# Main_Board_2X-SOLAR_5V-DCDC.net
KiCad netlist of a schematic drawn in EAGLE
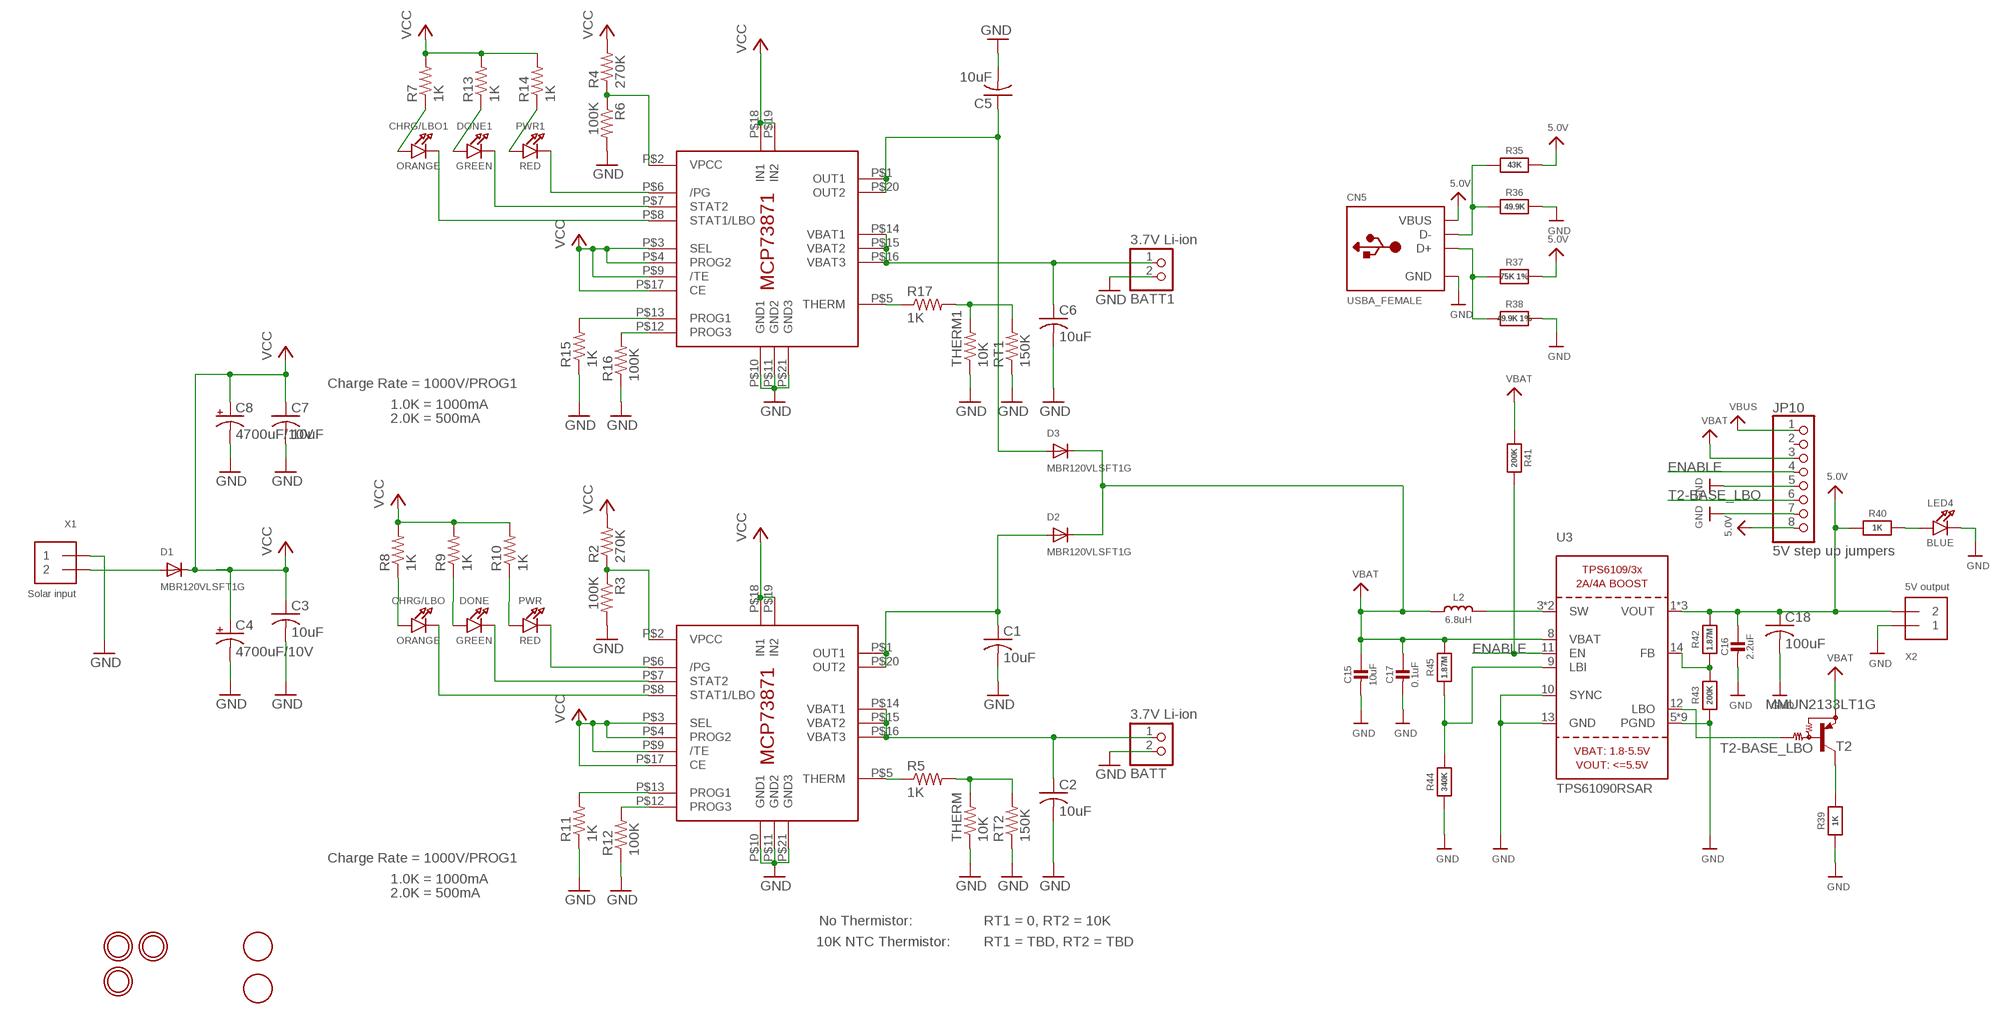
[diagram p0: schematic, sheet 1]

(export (version "E")
  (design (tool "Eeschema 10.0.6"))
  (components
    (comp (ref "BATT")
      (value "3.7V Li-ion")
      (footprint "eagle-import:JST-PH-2-SMT-RA")
      (libsource (lib "eagle-import") (part "JST_2PIN-SMT-RA"))
    )
    (comp (ref "BATT1")
      (value "3.7V Li-ion")
      (footprint "eagle-import:JST-PH-2-SMT-RA")
      (libsource (lib "eagle-import") (part "JST_2PIN-SMT-RA"))
    )
    (comp (ref "C1")
      (value "10uF")
      (footprint "eagle-import:C0805K")
      (libsource (lib "eagle-import") (part "C-USC0805K"))
    )
    (comp (ref "C2")
      (value "10uF")
      (footprint "eagle-import:C0805K")
      (libsource (lib "eagle-import") (part "C-USC0805K"))
    )
    (comp (ref "C3")
      (value "10uF")
      (footprint "eagle-import:C0805K")
      (libsource (lib "eagle-import") (part "C-USC0805K"))
    )
    (comp (ref "C4")
      (value "4700uF/10V")
      (footprint "eagle-import:E5-13")
      (libsource (lib "eagle-import") (part "CPOL-USE5-13"))
    )
    (comp (ref "C5")
      (value "10uF")
      (footprint "eagle-import:C0805K")
      (libsource (lib "eagle-import") (part "C-USC0805K"))
    )
    (comp (ref "C6")
      (value "10uF")
      (footprint "eagle-import:C0805K")
      (libsource (lib "eagle-import") (part "C-USC0805K"))
    )
    (comp (ref "C7")
      (value "10uF")
      (footprint "eagle-import:C0805K")
      (libsource (lib "eagle-import") (part "C-USC0805K"))
    )
    (comp (ref "C8")
      (value "4700uF/10V")
      (footprint "eagle-import:E5-13")
      (libsource (lib "eagle-import") (part "CPOL-USE5-13"))
    )
    (comp (ref "C15")
      (value "10uF")
      (footprint "eagle-import:0805-NO")
      (libsource (lib "eagle-import") (part "CAP_CERAMIC0805-NOOUTLINE"))
    )
    (comp (ref "C16")
      (value "2.2uF")
      (footprint "eagle-import:0805-NO")
      (libsource (lib "eagle-import") (part "CAP_CERAMIC0805-NOOUTLINE"))
    )
    (comp (ref "C17")
      (value "0.1uF")
      (footprint "eagle-import:0805_10MGAP")
      (libsource (lib "eagle-import") (part "CAP_CERAMIC0805_10MGAP"))
    )
    (comp (ref "C18")
      (value "100uF")
      (footprint "eagle-import:C1210")
      (libsource (lib "eagle-import") (part "rcl_C-USC1210"))
    )
    (comp (ref "CHRG/LBO")
      (value "ORANGE")
      (footprint "eagle-import:CHIPLED_0805_NOOUTLINE")
      (libsource (lib "eagle-import") (part "LED0805_NOOUTLINE"))
    )
    (comp (ref "CHRG/LBO1")
      (value "ORANGE")
      (footprint "eagle-import:CHIPLED_0805_NOOUTLINE")
      (libsource (lib "eagle-import") (part "LED0805_NOOUTLINE"))
    )
    (comp (ref "CN5")
      (value "USBA_FEMALE")
      (footprint "eagle-import:USB_HOST-PTH")
      (libsource (lib "eagle-import") (part "USB_TYPEAPTHFML"))
    )
    (comp (ref "D1")
      (value "MBR120VLSFT1G")
      (footprint "eagle-import:SOD-123")
      (libsource (lib "eagle-import") (part "DIODESOD-123"))
    )
    (comp (ref "D2")
      (value "MBR120VLSFT1G")
      (footprint "eagle-import:SOD-123")
      (libsource (lib "eagle-import") (part "DIODESOD-123"))
    )
    (comp (ref "D3")
      (value "MBR120VLSFT1G")
      (footprint "eagle-import:SOD-123")
      (libsource (lib "eagle-import") (part "DIODESOD-123"))
    )
    (comp (ref "DONE")
      (value "GREEN")
      (footprint "eagle-import:CHIPLED_0805_NOOUTLINE")
      (libsource (lib "eagle-import") (part "LED0805_NOOUTLINE"))
    )
    (comp (ref "DONE1")
      (value "GREEN")
      (footprint "eagle-import:CHIPLED_0805_NOOUTLINE")
      (libsource (lib "eagle-import") (part "LED0805_NOOUTLINE"))
    )
    (comp (ref "IC1")
      (value "MCP73871")
      (footprint "eagle-import:QFN20_4MM")
      (libsource (lib "eagle-import") (part "MCP73871"))
    )
    (comp (ref "IC2")
      (value "MCP73871")
      (footprint "eagle-import:QFN20_4MM")
      (libsource (lib "eagle-import") (part "MCP73871"))
    )
    (comp (ref "JP10")
      (value "5V step up jumpers")
      (footprint "eagle-import:1X08_ROUND")
      (libsource (lib "eagle-import") (part "HEADER-1X8ROUND"))
    )
    (comp (ref "L2")
      (value "6.8uH")
      (footprint "eagle-import:INDUCTOR_5X5MM_TDK_VLC5045")
      (libsource (lib "eagle-import") (part "INDUCTORTDK_VLC5045"))
    )
    (comp (ref "LED4")
      (value "BLUE")
      (footprint "eagle-import:CHIPLED_0805_NOOUTLINE")
      (libsource (lib "eagle-import") (part "LED0805_NOOUTLINE"))
    )
    (comp (ref "PWR")
      (value "RED")
      (footprint "eagle-import:CHIPLED_0805_NOOUTLINE")
      (libsource (lib "eagle-import") (part "LED0805_NOOUTLINE"))
    )
    (comp (ref "PWR1")
      (value "RED")
      (footprint "eagle-import:CHIPLED_0805_NOOUTLINE")
      (libsource (lib "eagle-import") (part "LED0805_NOOUTLINE"))
    )
    (comp (ref "R2")
      (value "270K")
      (footprint "eagle-import:R0805")
      (libsource (lib "eagle-import") (part "R-US_R0805"))
    )
    (comp (ref "R3")
      (value "100K")
      (footprint "eagle-import:R0805")
      (libsource (lib "eagle-import") (part "R-US_R0805"))
    )
    (comp (ref "R4")
      (value "270K")
      (footprint "eagle-import:R0805")
      (libsource (lib "eagle-import") (part "R-US_R0805"))
    )
    (comp (ref "R5")
      (value "1K")
      (footprint "eagle-import:M0805")
      (libsource (lib "eagle-import") (part "R-US_M0805"))
    )
    (comp (ref "R6")
      (value "100K")
      (footprint "eagle-import:R0805")
      (libsource (lib "eagle-import") (part "R-US_R0805"))
    )
    (comp (ref "R7")
      (value "1K")
      (footprint "eagle-import:R0805")
      (libsource (lib "eagle-import") (part "R-US_R0805"))
    )
    (comp (ref "R8")
      (value "1K")
      (footprint "eagle-import:R0805")
      (libsource (lib "eagle-import") (part "R-US_R0805"))
    )
    (comp (ref "R9")
      (value "1K")
      (footprint "eagle-import:R0805")
      (libsource (lib "eagle-import") (part "R-US_R0805"))
    )
    (comp (ref "R10")
      (value "1K")
      (footprint "eagle-import:R0805")
      (libsource (lib "eagle-import") (part "R-US_R0805"))
    )
    (comp (ref "R11")
      (value "1K")
      (footprint "eagle-import:0805-THM")
      (libsource (lib "eagle-import") (part "R-US_FLIPFLOP"))
    )
    (comp (ref "R12")
      (value "100K")
      (footprint "eagle-import:R0805")
      (libsource (lib "eagle-import") (part "R-US_R0805"))
    )
    (comp (ref "R13")
      (value "1K")
      (footprint "eagle-import:R0805")
      (libsource (lib "eagle-import") (part "R-US_R0805"))
    )
    (comp (ref "R14")
      (value "1K")
      (footprint "eagle-import:R0805")
      (libsource (lib "eagle-import") (part "R-US_R0805"))
    )
    (comp (ref "R15")
      (value "1K")
      (footprint "eagle-import:0805-THM")
      (libsource (lib "eagle-import") (part "R-US_FLIPFLOP"))
    )
    (comp (ref "R16")
      (value "100K")
      (footprint "eagle-import:R0805")
      (libsource (lib "eagle-import") (part "R-US_R0805"))
    )
    (comp (ref "R17")
      (value "1K")
      (footprint "eagle-import:M0805")
      (libsource (lib "eagle-import") (part "R-US_M0805"))
    )
    (comp (ref "R35")
      (value "43K")
      (footprint "eagle-import:0805-NO")
      (libsource (lib "eagle-import") (part "RESISTOR0805_NOOUTLINE"))
    )
    (comp (ref "R36")
      (value "49.9K")
      (footprint "eagle-import:0805-NO")
      (libsource (lib "eagle-import") (part "RESISTOR0805_NOOUTLINE"))
    )
    (comp (ref "R37")
      (value "75K 1%")
      (footprint "eagle-import:0805-NO")
      (libsource (lib "eagle-import") (part "RESISTOR0805_NOOUTLINE"))
    )
    (comp (ref "R38")
      (value "49.9K 1%")
      (footprint "eagle-import:0805-NO")
      (libsource (lib "eagle-import") (part "RESISTOR0805_NOOUTLINE"))
    )
    (comp (ref "R39")
      (value "1K")
      (footprint "eagle-import:0805-NO")
      (libsource (lib "eagle-import") (part "RESISTOR0805_NOOUTLINE"))
    )
    (comp (ref "R40")
      (value "1K")
      (footprint "eagle-import:0805-NO")
      (libsource (lib "eagle-import") (part "RESISTOR0805_NOOUTLINE"))
    )
    (comp (ref "R41")
      (value "200K")
      (footprint "eagle-import:0805-NO")
      (libsource (lib "eagle-import") (part "RESISTOR0805_NOOUTLINE"))
    )
    (comp (ref "R42")
      (value "1.87M")
      (footprint "eagle-import:0805-NO")
      (libsource (lib "eagle-import") (part "RESISTOR0805_NOOUTLINE"))
    )
    (comp (ref "R43")
      (value "200K")
      (footprint "eagle-import:0805-NO")
      (libsource (lib "eagle-import") (part "RESISTOR0805_NOOUTLINE"))
    )
    (comp (ref "R44")
      (value "340K")
      (footprint "eagle-import:_0805MP")
      (libsource (lib "eagle-import") (part "RESISTOR_0805MP"))
    )
    (comp (ref "R45")
      (value "1.87M")
      (footprint "eagle-import:_0805MP")
      (libsource (lib "eagle-import") (part "RESISTOR_0805MP"))
    )
    (comp (ref "RT1")
      (value "150K")
      (footprint "eagle-import:M0805")
      (libsource (lib "eagle-import") (part "R-US_M0805"))
    )
    (comp (ref "RT2")
      (value "150K")
      (footprint "eagle-import:M0805")
      (libsource (lib "eagle-import") (part "R-US_M0805"))
    )
    (comp (ref "T2")
      (value "MMUN2133LT1G")
      (footprint "eagle-import:SC59-BEC")
      (libsource (lib "eagle-import") (part "-PNP_DRIVER-SC59-BECMUN2114T1"))
    )
    (comp (ref "THERM")
      (value "10K")
      (footprint "eagle-import:0805-THM")
      (libsource (lib "eagle-import") (part "R-US_FLIPFLOP"))
    )
    (comp (ref "THERM1")
      (value "10K")
      (footprint "eagle-import:0805-THM")
      (libsource (lib "eagle-import") (part "R-US_FLIPFLOP"))
    )
    (comp (ref "U$1")
      (value "MOUNTINGHOLE2.5")
      (footprint "eagle-import:MOUNTINGHOLE_2.5_PLATED")
      (libsource (lib "eagle-import") (part "MOUNTINGHOLE2.5"))
    )
    (comp (ref "U$3")
      (value "FIDUCIAL")
      (footprint "eagle-import:FIDUCIAL_1MM")
      (libsource (lib "eagle-import") (part "FIDUCIAL"))
    )
    (comp (ref "U$4")
      (value "MOUNTINGHOLE2.5")
      (footprint "eagle-import:MOUNTINGHOLE_2.5_PLATED")
      (libsource (lib "eagle-import") (part "MOUNTINGHOLE2.5"))
    )
    (comp (ref "U$6")
      (value "MOUNTINGHOLE2.5")
      (footprint "eagle-import:MOUNTINGHOLE_2.5_PLATED")
      (libsource (lib "eagle-import") (part "MOUNTINGHOLE2.5"))
    )
    (comp (ref "U$8")
      (value "FIDUCIAL")
      (footprint "eagle-import:FIDUCIAL_1MM")
      (libsource (lib "eagle-import") (part "FIDUCIAL"))
    )
    (comp (ref "U3")
      (value "TPS61090RSAR")
      (footprint "eagle-import:PVQFN-16")
      (libsource (lib "eagle-import") (part "VREG_TPS6103X"))
    )
    (comp (ref "X1")
      (value "Solar input")
      (footprint "eagle-import:TERMBLOCK_1X2-3.5MM")
      (libsource (lib "eagle-import") (part "TERMBLOCK_1X2"))
    )
    (comp (ref "X2")
      (value "5V output")
      (footprint "eagle-import:TERMBLOCK_1X2-3.5MM")
      (libsource (lib "eagle-import") (part "TERMBLOCK_1X2"))
    )
  )
  (nets
    (net (code "1") (name "/ENABLE") (class "Default")
      (node (ref "JP10") (pin "4") (pinfunction "4_4") (pintype "passive"))
      (node (ref "R41") (pin "2") (pinfunction "2_2") (pintype "passive"))
      (node (ref "U3") (pin "11") (pinfunction "EN_11") (pintype "input"))
    )
    (net (code "2") (name "/T2-BASE_LBO") (class "Default")
      (node (ref "JP10") (pin "6") (pinfunction "6_6") (pintype "passive"))
      (node (ref "T2") (pin "B") (pinfunction "B_B") (pintype "passive"))
      (node (ref "U3") (pin "12") (pinfunction "LBO_12") (pintype "output"))
    )
    (net (code "3") (name "5.0V") (class "Default")
      (node (ref "C16") (pin "1") (pinfunction "1_1") (pintype "passive"))
      (node (ref "C18") (pin "1") (pinfunction "1_1") (pintype "passive"))
      (node (ref "CN5") (pin "VBUS") (pinfunction "VBUS_VBUS") (pintype "power_in"))
      (node (ref "JP10") (pin "8") (pinfunction "8_8") (pintype "passive"))
      (node (ref "R35") (pin "2") (pinfunction "2_2") (pintype "passive"))
      (node (ref "R37") (pin "2") (pinfunction "2_2") (pintype "passive"))
      (node (ref "R40") (pin "1") (pinfunction "1_1") (pintype "passive"))
      (node (ref "R42") (pin "2") (pinfunction "2_2") (pintype "passive"))
      (node (ref "U3") (pin "1") (pinfunction "VOUT_1") (pintype "power_in"))
      (node (ref "U3") (pin "15") (pinfunction "VOUT_15") (pintype "power_in"))
      (node (ref "U3") (pin "16") (pinfunction "VOUT_16") (pintype "power_in"))
      (node (ref "X2") (pin "2") (pinfunction "2_2") (pintype "passive"))
    )
    (net (code "4") (name "GND") (class "Default")
      (node (ref "BATT") (pin "2") (pinfunction "1_2") (pintype "passive"))
      (node (ref "BATT1") (pin "2") (pinfunction "1_2") (pintype "passive"))
      (node (ref "C1") (pin "2") (pinfunction "2_2") (pintype "passive"))
      (node (ref "C15") (pin "2") (pinfunction "2_2") (pintype "passive"))
      (node (ref "C16") (pin "2") (pinfunction "2_2") (pintype "passive"))
      (node (ref "C17") (pin "2") (pinfunction "2_2") (pintype "passive"))
      (node (ref "C18") (pin "2") (pinfunction "2_2") (pintype "passive"))
      (node (ref "C2") (pin "2") (pinfunction "2_2") (pintype "passive"))
      (node (ref "C3") (pin "2") (pinfunction "2_2") (pintype "passive"))
      (node (ref "C4") (pin "-") (pinfunction "-_-") (pintype "passive"))
      (node (ref "C5") (pin "2") (pinfunction "2_2") (pintype "passive"))
      (node (ref "C6") (pin "2") (pinfunction "2_2") (pintype "passive"))
      (node (ref "C7") (pin "2") (pinfunction "2_2") (pintype "passive"))
      (node (ref "C8") (pin "-") (pinfunction "-_-") (pintype "passive"))
      (node (ref "CN5") (pin "GND") (pinfunction "GND_GND") (pintype "power_in"))
      (node (ref "IC1") (pin "P$10") (pinfunction "GND1_P$10") (pintype "power_in"))
      (node (ref "IC1") (pin "P$11") (pinfunction "GND2_P$11") (pintype "power_in"))
      (node (ref "IC1") (pin "P$21") (pinfunction "GND3_P$21") (pintype "power_in"))
      (node (ref "IC2") (pin "P$10") (pinfunction "GND1_P$10") (pintype "power_in"))
      (node (ref "IC2") (pin "P$11") (pinfunction "GND2_P$11") (pintype "power_in"))
      (node (ref "IC2") (pin "P$21") (pinfunction "GND3_P$21") (pintype "power_in"))
      (node (ref "JP10") (pin "5") (pinfunction "5_5") (pintype "passive"))
      (node (ref "JP10") (pin "7") (pinfunction "7_7") (pintype "passive"))
      (node (ref "LED4") (pin "C") (pinfunction "C_C") (pintype "passive"))
      (node (ref "R11") (pin "1") (pinfunction "1_1") (pintype "passive"))
      (node (ref "R12") (pin "1") (pinfunction "1_1") (pintype "passive"))
      (node (ref "R15") (pin "1") (pinfunction "1_1") (pintype "passive"))
      (node (ref "R16") (pin "1") (pinfunction "1_1") (pintype "passive"))
      (node (ref "R3") (pin "2") (pinfunction "2_2") (pintype "passive"))
      (node (ref "R36") (pin "2") (pinfunction "2_2") (pintype "passive"))
      (node (ref "R38") (pin "2") (pinfunction "2_2") (pintype "passive"))
      (node (ref "R39") (pin "1") (pinfunction "1_1") (pintype "passive"))
      (node (ref "R43") (pin "1") (pinfunction "1_1") (pintype "passive"))
      (node (ref "R44") (pin "1") (pinfunction "1_1") (pintype "passive"))
      (node (ref "R6") (pin "2") (pinfunction "2_2") (pintype "passive"))
      (node (ref "RT1") (pin "1") (pinfunction "1_1") (pintype "passive"))
      (node (ref "RT2") (pin "1") (pinfunction "1_1") (pintype "passive"))
      (node (ref "THERM") (pin "1") (pinfunction "1_1") (pintype "passive"))
      (node (ref "THERM1") (pin "1") (pinfunction "1_1") (pintype "passive"))
      (node (ref "U3") (pin "10") (pinfunction "SYNC_10") (pintype "input"))
      (node (ref "U3") (pin "13") (pinfunction "GND_13") (pintype "power_in"))
      (node (ref "U3") (pin "5") (pinfunction "PGND_5") (pintype "power_in"))
      (node (ref "U3") (pin "6") (pinfunction "PGND_6") (pintype "power_in"))
      (node (ref "U3") (pin "7") (pinfunction "PGND_7") (pintype "power_in"))
      (node (ref "U3") (pin "P$18") (pinfunction "PGND_P$18") (pintype "power_in"))
      (node (ref "U3") (pin "P$19") (pinfunction "PGND_P$19") (pintype "power_in"))
      (node (ref "U3") (pin "P$20") (pinfunction "PGND_P$20") (pintype "power_in"))
      (node (ref "U3") (pin "P$21") (pinfunction "PGND_P$21") (pintype "power_in"))
      (node (ref "U3") (pin "P$22") (pinfunction "PGND_P$22") (pintype "power_in"))
      (node (ref "U3") (pin "THERMAL") (pinfunction "PGND_THERMAL") (pintype "power_in"))
      (node (ref "X1") (pin "1") (pinfunction "1_1") (pintype "passive"))
      (node (ref "X2") (pin "1") (pinfunction "1_1") (pintype "passive"))
    )
    (net (code "5") (name "Net-(BATT-2)") (class "Default")
      (node (ref "BATT") (pin "1") (pinfunction "2_1") (pintype "passive"))
      (node (ref "C2") (pin "1") (pinfunction "1_1") (pintype "passive"))
      (node (ref "IC1") (pin "P$14") (pinfunction "VBAT1_P$14") (pintype "output"))
      (node (ref "IC1") (pin "P$15") (pinfunction "VBAT2_P$15") (pintype "output"))
      (node (ref "IC1") (pin "P$16") (pinfunction "VBAT3_P$16") (pintype "output"))
    )
    (net (code "6") (name "Net-(BATT1-2)") (class "Default")
      (node (ref "BATT1") (pin "1") (pinfunction "2_1") (pintype "passive"))
      (node (ref "C6") (pin "1") (pinfunction "1_1") (pintype "passive"))
      (node (ref "IC2") (pin "P$14") (pinfunction "VBAT1_P$14") (pintype "output"))
      (node (ref "IC2") (pin "P$15") (pinfunction "VBAT2_P$15") (pintype "output"))
      (node (ref "IC2") (pin "P$16") (pinfunction "VBAT3_P$16") (pintype "output"))
    )
    (net (code "7") (name "Net-(CHRG/LBO-PadA)") (class "Default")
      (node (ref "CHRG/LBO") (pin "A") (pinfunction "A_A") (pintype "passive"))
      (node (ref "R8") (pin "1") (pinfunction "1_1") (pintype "passive"))
    )
    (net (code "8") (name "Net-(CHRG/LBO1-PadA)") (class "Default")
      (node (ref "CHRG/LBO1") (pin "A") (pinfunction "A_A") (pintype "passive"))
      (node (ref "R7") (pin "1") (pinfunction "1_1") (pintype "passive"))
    )
    (net (code "9") (name "Net-(CN5-PadD+)") (class "Default")
      (node (ref "CN5") (pin "D+") (pinfunction "D+_D+") (pintype "bidirectional"))
      (node (ref "R37") (pin "1") (pinfunction "1_1") (pintype "passive"))
      (node (ref "R38") (pin "1") (pinfunction "1_1") (pintype "passive"))
    )
    (net (code "10") (name "Net-(CN5-PadD-)") (class "Default")
      (node (ref "CN5") (pin "D-") (pinfunction "D-_D-") (pintype "bidirectional"))
      (node (ref "R35") (pin "1") (pinfunction "1_1") (pintype "passive"))
      (node (ref "R36") (pin "1") (pinfunction "1_1") (pintype "passive"))
    )
    (net (code "11") (name "Net-(D1-PadA)") (class "Default")
      (node (ref "D1") (pin "A") (pinfunction "A_A") (pintype "passive"))
      (node (ref "X1") (pin "2") (pinfunction "2_2") (pintype "passive"))
    )
    (net (code "12") (name "Net-(DONE-PadA)") (class "Default")
      (node (ref "DONE") (pin "A") (pinfunction "A_A") (pintype "passive"))
      (node (ref "R9") (pin "1") (pinfunction "1_1") (pintype "passive"))
    )
    (net (code "13") (name "Net-(DONE1-PadA)") (class "Default")
      (node (ref "DONE1") (pin "A") (pinfunction "A_A") (pintype "passive"))
      (node (ref "R13") (pin "1") (pinfunction "1_1") (pintype "passive"))
    )
    (net (code "14") (name "Net-(IC1-OUT1)") (class "Default")
      (node (ref "C1") (pin "1") (pinfunction "1_1") (pintype "passive"))
      (node (ref "D2") (pin "A") (pinfunction "A_A") (pintype "passive"))
      (node (ref "IC1") (pin "P$1") (pinfunction "OUT1_P$1") (pintype "output"))
      (node (ref "IC1") (pin "P$20") (pinfunction "OUT2_P$20") (pintype "output"))
    )
    (net (code "15") (name "Net-(IC1-PROG1)") (class "Default")
      (node (ref "IC1") (pin "P$13") (pinfunction "PROG1_P$13") (pintype "input"))
      (node (ref "R11") (pin "2") (pinfunction "2_2") (pintype "passive"))
    )
    (net (code "16") (name "Net-(IC1-PROG3)") (class "Default")
      (node (ref "IC1") (pin "P$12") (pinfunction "PROG3_P$12") (pintype "input"))
      (node (ref "R12") (pin "2") (pinfunction "2_2") (pintype "passive"))
    )
    (net (code "17") (name "Net-(IC1-STAT1{slash}LBO)") (class "Default")
      (node (ref "CHRG/LBO") (pin "C") (pinfunction "C_C") (pintype "passive"))
      (node (ref "IC1") (pin "P$8") (pinfunction "STAT1/LBO_P$8") (pintype "output"))
    )
    (net (code "18") (name "Net-(IC1-STAT2)") (class "Default")
      (node (ref "DONE") (pin "C") (pinfunction "C_C") (pintype "passive"))
      (node (ref "IC1") (pin "P$7") (pinfunction "STAT2_P$7") (pintype "output"))
    )
    (net (code "19") (name "Net-(IC1-THERM)") (class "Default")
      (node (ref "IC1") (pin "P$5") (pinfunction "THERM_P$5") (pintype "input"))
      (node (ref "R5") (pin "1") (pinfunction "1_1") (pintype "passive"))
    )
    (net (code "20") (name "Net-(IC1-VPCC)") (class "Default")
      (node (ref "IC1") (pin "P$2") (pinfunction "VPCC_P$2") (pintype "input"))
      (node (ref "R2") (pin "1") (pinfunction "1_1") (pintype "passive"))
      (node (ref "R3") (pin "1") (pinfunction "1_1") (pintype "passive"))
    )
    (net (code "21") (name "Net-(IC1-{slash}PG)") (class "Default")
      (node (ref "IC1") (pin "P$6") (pinfunction "/PG_P$6") (pintype "output"))
      (node (ref "PWR") (pin "C") (pinfunction "C_C") (pintype "passive"))
    )
    (net (code "22") (name "Net-(IC2-OUT1)") (class "Default")
      (node (ref "C5") (pin "1") (pinfunction "1_1") (pintype "passive"))
      (node (ref "D3") (pin "A") (pinfunction "A_A") (pintype "passive"))
      (node (ref "IC2") (pin "P$1") (pinfunction "OUT1_P$1") (pintype "output"))
      (node (ref "IC2") (pin "P$20") (pinfunction "OUT2_P$20") (pintype "output"))
    )
    (net (code "23") (name "Net-(IC2-PROG1)") (class "Default")
      (node (ref "IC2") (pin "P$13") (pinfunction "PROG1_P$13") (pintype "input"))
      (node (ref "R15") (pin "2") (pinfunction "2_2") (pintype "passive"))
    )
    (net (code "24") (name "Net-(IC2-PROG3)") (class "Default")
      (node (ref "IC2") (pin "P$12") (pinfunction "PROG3_P$12") (pintype "input"))
      (node (ref "R16") (pin "2") (pinfunction "2_2") (pintype "passive"))
    )
    (net (code "25") (name "Net-(IC2-STAT1{slash}LBO)") (class "Default")
      (node (ref "CHRG/LBO1") (pin "C") (pinfunction "C_C") (pintype "passive"))
      (node (ref "IC2") (pin "P$8") (pinfunction "STAT1/LBO_P$8") (pintype "output"))
    )
    (net (code "26") (name "Net-(IC2-STAT2)") (class "Default")
      (node (ref "DONE1") (pin "C") (pinfunction "C_C") (pintype "passive"))
      (node (ref "IC2") (pin "P$7") (pinfunction "STAT2_P$7") (pintype "output"))
    )
    (net (code "27") (name "Net-(IC2-THERM)") (class "Default")
      (node (ref "IC2") (pin "P$5") (pinfunction "THERM_P$5") (pintype "input"))
      (node (ref "R17") (pin "1") (pinfunction "1_1") (pintype "passive"))
    )
    (net (code "28") (name "Net-(IC2-VPCC)") (class "Default")
      (node (ref "IC2") (pin "P$2") (pinfunction "VPCC_P$2") (pintype "input"))
      (node (ref "R4") (pin "1") (pinfunction "1_1") (pintype "passive"))
      (node (ref "R6") (pin "1") (pinfunction "1_1") (pintype "passive"))
    )
    (net (code "29") (name "Net-(IC2-{slash}PG)") (class "Default")
      (node (ref "IC2") (pin "P$6") (pinfunction "/PG_P$6") (pintype "output"))
      (node (ref "PWR1") (pin "C") (pinfunction "C_C") (pintype "passive"))
    )
    (net (code "30") (name "Net-(L2-2)") (class "Default")
      (node (ref "L2") (pin "P$2") (pinfunction "2_P$2") (pintype "passive"))
      (node (ref "U3") (pin "3") (pinfunction "SW_3") (pintype "input"))
      (node (ref "U3") (pin "4") (pinfunction "SW_4") (pintype "input"))
    )
    (net (code "31") (name "Net-(LED4-PadA)") (class "Default")
      (node (ref "LED4") (pin "A") (pinfunction "A_A") (pintype "passive"))
      (node (ref "R40") (pin "2") (pinfunction "2_2") (pintype "passive"))
    )
    (net (code "32") (name "Net-(PWR-PadA)") (class "Default")
      (node (ref "PWR") (pin "A") (pinfunction "A_A") (pintype "passive"))
      (node (ref "R10") (pin "1") (pinfunction "1_1") (pintype "passive"))
    )
    (net (code "33") (name "Net-(PWR1-PadA)") (class "Default")
      (node (ref "PWR1") (pin "A") (pinfunction "A_A") (pintype "passive"))
      (node (ref "R14") (pin "1") (pinfunction "1_1") (pintype "passive"))
    )
    (net (code "34") (name "Net-(R5-Pad2)") (class "Default")
      (node (ref "R5") (pin "2") (pinfunction "2_2") (pintype "passive"))
      (node (ref "RT2") (pin "2") (pinfunction "2_2") (pintype "passive"))
      (node (ref "THERM") (pin "2") (pinfunction "2_2") (pintype "passive"))
    )
    (net (code "35") (name "Net-(R17-Pad2)") (class "Default")
      (node (ref "R17") (pin "2") (pinfunction "2_2") (pintype "passive"))
      (node (ref "RT1") (pin "2") (pinfunction "2_2") (pintype "passive"))
      (node (ref "THERM1") (pin "2") (pinfunction "2_2") (pintype "passive"))
    )
    (net (code "36") (name "Net-(R39-Pad2)") (class "Default")
      (node (ref "R39") (pin "2") (pinfunction "2_2") (pintype "passive"))
      (node (ref "T2") (pin "C") (pinfunction "C_C") (pintype "passive"))
    )
    (net (code "37") (name "Net-(U3-FB)") (class "Default")
      (node (ref "R42") (pin "1") (pinfunction "1_1") (pintype "passive"))
      (node (ref "R43") (pin "2") (pinfunction "2_2") (pintype "passive"))
      (node (ref "U3") (pin "14") (pinfunction "FB_14") (pintype "input"))
    )
    (net (code "38") (name "Net-(U3-LBI)") (class "Default")
      (node (ref "R44") (pin "2") (pinfunction "2_2") (pintype "passive"))
      (node (ref "R45") (pin "1") (pinfunction "1_1") (pintype "passive"))
      (node (ref "U3") (pin "9") (pinfunction "LBI_9") (pintype "input"))
    )
    (net (code "39") (name "VBAT") (class "Default")
      (node (ref "C15") (pin "1") (pinfunction "1_1") (pintype "passive"))
      (node (ref "C17") (pin "1") (pinfunction "1_1") (pintype "passive"))
      (node (ref "D2") (pin "C") (pinfunction "C_C") (pintype "passive"))
      (node (ref "D3") (pin "C") (pinfunction "C_C") (pintype "passive"))
      (node (ref "JP10") (pin "3") (pinfunction "3_3") (pintype "passive"))
      (node (ref "L2") (pin "P$1") (pinfunction "1_P$1") (pintype "passive"))
      (node (ref "R41") (pin "1") (pinfunction "1_1") (pintype "passive"))
      (node (ref "R45") (pin "2") (pinfunction "2_2") (pintype "passive"))
      (node (ref "T2") (pin "E") (pinfunction "E_E") (pintype "passive"))
      (node (ref "U3") (pin "8") (pinfunction "VBAT_8") (pintype "input"))
    )
    (net (code "40") (name "VBUS") (class "Default")
      (node (ref "JP10") (pin "1") (pinfunction "1_1") (pintype "passive"))
    )
    (net (code "41") (name "VCC") (class "Default")
      (node (ref "C3") (pin "1") (pinfunction "1_1") (pintype "passive"))
      (node (ref "C4") (pin "+") (pinfunction "+_+") (pintype "passive"))
      (node (ref "C7") (pin "1") (pinfunction "1_1") (pintype "passive"))
      (node (ref "C8") (pin "+") (pinfunction "+_+") (pintype "passive"))
      (node (ref "D1") (pin "C") (pinfunction "C_C") (pintype "passive"))
      (node (ref "IC1") (pin "P$17") (pinfunction "CE_P$17") (pintype "input"))
      (node (ref "IC1") (pin "P$18") (pinfunction "IN1_P$18") (pintype "input"))
      (node (ref "IC1") (pin "P$19") (pinfunction "IN2_P$19") (pintype "input"))
      (node (ref "IC1") (pin "P$3") (pinfunction "SEL_P$3") (pintype "input"))
      (node (ref "IC1") (pin "P$4") (pinfunction "PROG2_P$4") (pintype "input"))
      (node (ref "IC1") (pin "P$9") (pinfunction "/TE_P$9") (pintype "input"))
      (node (ref "IC2") (pin "P$17") (pinfunction "CE_P$17") (pintype "input"))
      (node (ref "IC2") (pin "P$18") (pinfunction "IN1_P$18") (pintype "input"))
      (node (ref "IC2") (pin "P$19") (pinfunction "IN2_P$19") (pintype "input"))
      (node (ref "IC2") (pin "P$3") (pinfunction "SEL_P$3") (pintype "input"))
      (node (ref "IC2") (pin "P$4") (pinfunction "PROG2_P$4") (pintype "input"))
      (node (ref "IC2") (pin "P$9") (pinfunction "/TE_P$9") (pintype "input"))
      (node (ref "R10") (pin "2") (pinfunction "2_2") (pintype "passive"))
      (node (ref "R13") (pin "2") (pinfunction "2_2") (pintype "passive"))
      (node (ref "R14") (pin "2") (pinfunction "2_2") (pintype "passive"))
      (node (ref "R2") (pin "2") (pinfunction "2_2") (pintype "passive"))
      (node (ref "R4") (pin "2") (pinfunction "2_2") (pintype "passive"))
      (node (ref "R7") (pin "2") (pinfunction "2_2") (pintype "passive"))
      (node (ref "R8") (pin "2") (pinfunction "2_2") (pintype "passive"))
      (node (ref "R9") (pin "2") (pinfunction "2_2") (pintype "passive"))
    )
    (net (code "42") (name "unconnected-(JP10-Pad2)") (class "Default")
      (node (ref "JP10") (pin "2") (pinfunction "2_2") (pintype "passive"))
    )
  )
)
